# LNetPanel.net
KiCad netlist of a schematic drawn in EAGLE
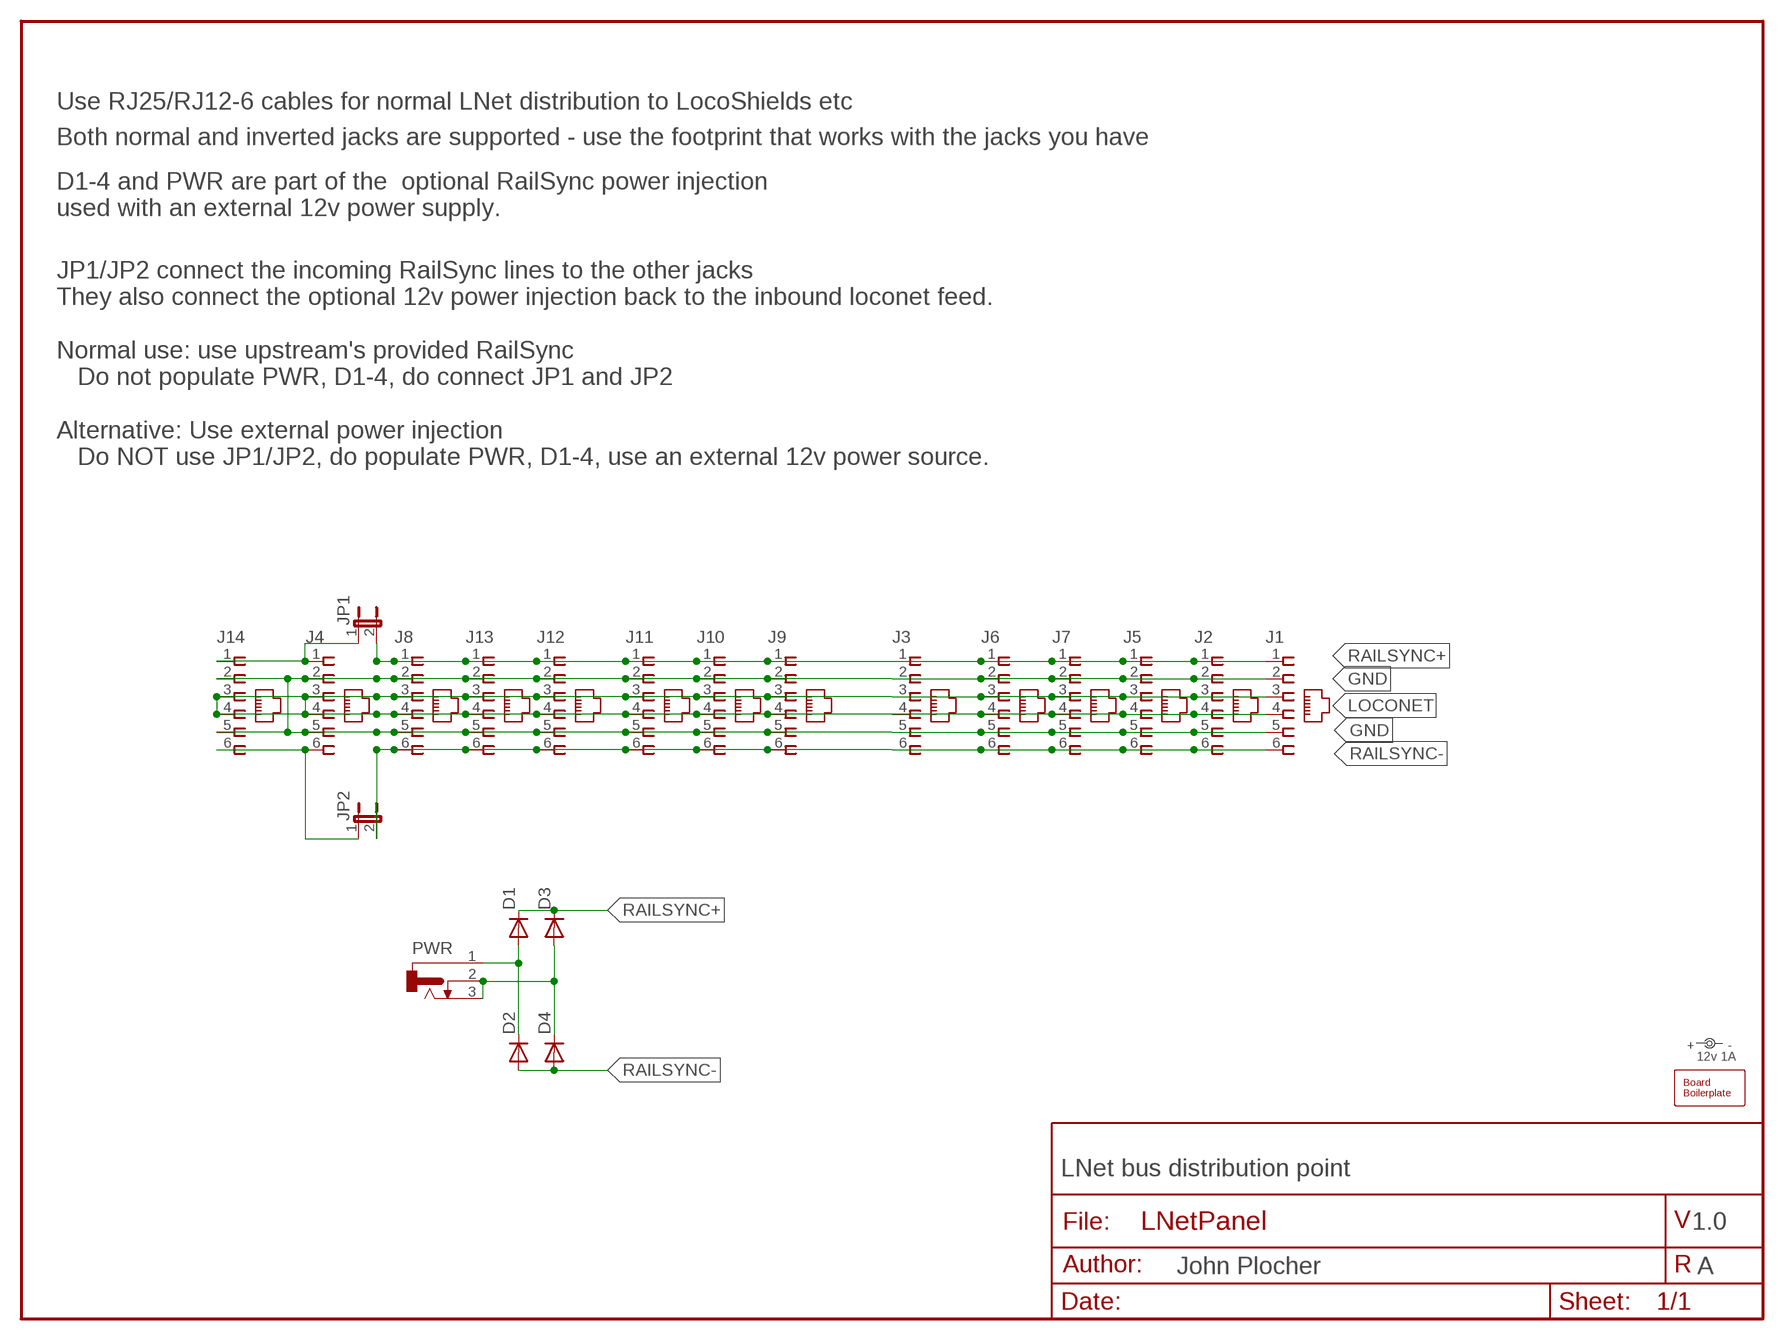
[diagram p0: schematic, sheet 1]

(export (version "E")
  (design (tool "Eeschema 10.0.6"))
  (components
    (comp (ref "D1")
      (value "DIODEPTH")
      (footprint "eagle-import:DIODE-1N4001")
      (libsource (lib "eagle-import") (part "DIODEPTH"))
    )
    (comp (ref "D2")
      (value "DIODEPTH")
      (footprint "eagle-import:DIODE-1N4001")
      (libsource (lib "eagle-import") (part "DIODEPTH"))
    )
    (comp (ref "D3")
      (value "DIODEPTH")
      (footprint "eagle-import:DIODE-1N4001")
      (libsource (lib "eagle-import") (part "DIODEPTH"))
    )
    (comp (ref "D4")
      (value "DIODEPTH")
      (footprint "eagle-import:DIODE-1N4001")
      (libsource (lib "eagle-import") (part "DIODEPTH"))
    )
    (comp (ref "J1")
      (value "CONNECTOR-RJ25-43860-2-MOLEX")
      (footprint "eagle-import:RJ25-INVERTED")
      (libsource (lib "eagle-import") (part "CONNECTOR-RJ25-43860-2-MOLEX"))
    )
    (comp (ref "J2")
      (value "CONNECTOR-RJ25-43860-2-MOLEX")
      (footprint "eagle-import:RJ25-INVERTED")
      (libsource (lib "eagle-import") (part "CONNECTOR-RJ25-43860-2-MOLEX"))
    )
    (comp (ref "J3")
      (value "CONNECTOR-RJ25-43860-2-MOLEX")
      (footprint "eagle-import:RJ25-INVERTED")
      (libsource (lib "eagle-import") (part "CONNECTOR-RJ25-43860-2-MOLEX"))
    )
    (comp (ref "J4")
      (value "CONNECTOR-RJ25-43860-2-MOLEX")
      (footprint "eagle-import:RJ25-INVERTED")
      (libsource (lib "eagle-import") (part "CONNECTOR-RJ25-43860-2-MOLEX"))
    )
    (comp (ref "J5")
      (value "CONNECTOR-RJ25-43860-2-MOLEX")
      (footprint "eagle-import:RJ25-INVERTED")
      (libsource (lib "eagle-import") (part "CONNECTOR-RJ25-43860-2-MOLEX"))
    )
    (comp (ref "J6")
      (value "CONNECTOR-RJ25-43860-2-MOLEX")
      (footprint "eagle-import:RJ25-INVERTED")
      (libsource (lib "eagle-import") (part "CONNECTOR-RJ25-43860-2-MOLEX"))
    )
    (comp (ref "J7")
      (value "CONNECTOR-RJ25-43860-2-MOLEX")
      (footprint "eagle-import:RJ25-INVERTED")
      (libsource (lib "eagle-import") (part "CONNECTOR-RJ25-43860-2-MOLEX"))
    )
    (comp (ref "J8")
      (value "CONNECTOR-RJ25AMP")
      (footprint "eagle-import:RJ25-PANEL")
      (libsource (lib "eagle-import") (part "CONNECTOR-RJ25AMP"))
    )
    (comp (ref "J9")
      (value "CONNECTOR-RJ25AMP")
      (footprint "eagle-import:RJ25-PANEL")
      (libsource (lib "eagle-import") (part "CONNECTOR-RJ25AMP"))
    )
    (comp (ref "J10")
      (value "CONNECTOR-RJ25AMP")
      (footprint "eagle-import:RJ25-PANEL")
      (libsource (lib "eagle-import") (part "CONNECTOR-RJ25AMP"))
    )
    (comp (ref "J11")
      (value "CONNECTOR-RJ25AMP")
      (footprint "eagle-import:RJ25-PANEL")
      (libsource (lib "eagle-import") (part "CONNECTOR-RJ25AMP"))
    )
    (comp (ref "J12")
      (value "CONNECTOR-RJ25AMP")
      (footprint "eagle-import:RJ25-PANEL")
      (libsource (lib "eagle-import") (part "CONNECTOR-RJ25AMP"))
    )
    (comp (ref "J13")
      (value "CONNECTOR-RJ25AMP")
      (footprint "eagle-import:RJ25-PANEL")
      (libsource (lib "eagle-import") (part "CONNECTOR-RJ25AMP"))
    )
    (comp (ref "J14")
      (value "CONNECTOR-RJ25AMP")
      (footprint "eagle-import:RJ25-PANEL")
      (libsource (lib "eagle-import") (part "CONNECTOR-RJ25AMP"))
    )
    (comp (ref "JP1")
      (value "JUMPER-2PTH_LOCK")
      (footprint "eagle-import:1X02_LOCK")
      (libsource (lib "eagle-import") (part "JUMPER-2PTH_LOCK"))
    )
    (comp (ref "JP2")
      (value "JUMPER-2PTH_LOCK")
      (footprint "eagle-import:1X02_LOCK")
      (libsource (lib "eagle-import") (part "JUMPER-2PTH_LOCK"))
    )
    (comp (ref "PWR")
      (value "CONNECTOR-DC-POWER-RA")
      (footprint "eagle-import:DCJ0202")
      (libsource (lib "eagle-import") (part "CONNECTOR-DC-POWER-RA"))
    )
    (comp (ref "U$1")
      (value "BOARD50X50-HOHOLES")
      (footprint "eagle-import:BOARD-SEEED7X7")
      (libsource (lib "eagle-import") (part "BOARD70X70"))
    )
    (comp (ref "U$2")
      (value "12v 1A")
      (footprint "eagle-import:POWER_USAGE")
      (libsource (lib "eagle-import") (part "DOC-POWER_LABEL"))
    )
  )
  (nets
    (net (code "1") (name "GND") (class "Default")
      (node (ref "J1") (pin "2") (pinfunction "2_2") (pintype "passive"))
      (node (ref "J1") (pin "5") (pinfunction "5_5") (pintype "passive"))
      (node (ref "J10") (pin "2") (pinfunction "2_2") (pintype "passive"))
      (node (ref "J10") (pin "5") (pinfunction "5_5") (pintype "passive"))
      (node (ref "J11") (pin "2") (pinfunction "2_2") (pintype "passive"))
      (node (ref "J11") (pin "5") (pinfunction "5_5") (pintype "passive"))
      (node (ref "J12") (pin "2") (pinfunction "2_2") (pintype "passive"))
      (node (ref "J12") (pin "5") (pinfunction "5_5") (pintype "passive"))
      (node (ref "J13") (pin "2") (pinfunction "2_2") (pintype "passive"))
      (node (ref "J13") (pin "5") (pinfunction "5_5") (pintype "passive"))
      (node (ref "J14") (pin "2") (pinfunction "2_2") (pintype "passive"))
      (node (ref "J14") (pin "5") (pinfunction "5_5") (pintype "passive"))
      (node (ref "J2") (pin "2") (pinfunction "2_2") (pintype "passive"))
      (node (ref "J2") (pin "5") (pinfunction "5_5") (pintype "passive"))
      (node (ref "J3") (pin "2") (pinfunction "2_2") (pintype "passive"))
      (node (ref "J3") (pin "5") (pinfunction "5_5") (pintype "passive"))
      (node (ref "J4") (pin "2") (pinfunction "2_2") (pintype "passive"))
      (node (ref "J4") (pin "5") (pinfunction "5_5") (pintype "passive"))
      (node (ref "J5") (pin "2") (pinfunction "2_2") (pintype "passive"))
      (node (ref "J5") (pin "5") (pinfunction "5_5") (pintype "passive"))
      (node (ref "J6") (pin "2") (pinfunction "2_2") (pintype "passive"))
      (node (ref "J6") (pin "5") (pinfunction "5_5") (pintype "passive"))
      (node (ref "J7") (pin "2") (pinfunction "2_2") (pintype "passive"))
      (node (ref "J7") (pin "5") (pinfunction "5_5") (pintype "passive"))
      (node (ref "J8") (pin "2") (pinfunction "2_2") (pintype "passive"))
      (node (ref "J8") (pin "5") (pinfunction "5_5") (pintype "passive"))
      (node (ref "J9") (pin "2") (pinfunction "2_2") (pintype "passive"))
      (node (ref "J9") (pin "5") (pinfunction "5_5") (pintype "passive"))
    )
    (net (code "2") (name "LOCONET") (class "Default")
      (node (ref "J1") (pin "3") (pinfunction "3_3") (pintype "passive"))
      (node (ref "J1") (pin "4") (pinfunction "4_4") (pintype "passive"))
      (node (ref "J10") (pin "3") (pinfunction "3_3") (pintype "passive"))
      (node (ref "J10") (pin "4") (pinfunction "4_4") (pintype "passive"))
      (node (ref "J11") (pin "3") (pinfunction "3_3") (pintype "passive"))
      (node (ref "J11") (pin "4") (pinfunction "4_4") (pintype "passive"))
      (node (ref "J12") (pin "3") (pinfunction "3_3") (pintype "passive"))
      (node (ref "J12") (pin "4") (pinfunction "4_4") (pintype "passive"))
      (node (ref "J13") (pin "3") (pinfunction "3_3") (pintype "passive"))
      (node (ref "J13") (pin "4") (pinfunction "4_4") (pintype "passive"))
      (node (ref "J14") (pin "3") (pinfunction "3_3") (pintype "passive"))
      (node (ref "J14") (pin "4") (pinfunction "4_4") (pintype "passive"))
      (node (ref "J2") (pin "3") (pinfunction "3_3") (pintype "passive"))
      (node (ref "J2") (pin "4") (pinfunction "4_4") (pintype "passive"))
      (node (ref "J3") (pin "3") (pinfunction "3_3") (pintype "passive"))
      (node (ref "J3") (pin "4") (pinfunction "4_4") (pintype "passive"))
      (node (ref "J4") (pin "3") (pinfunction "3_3") (pintype "passive"))
      (node (ref "J4") (pin "4") (pinfunction "4_4") (pintype "passive"))
      (node (ref "J5") (pin "3") (pinfunction "3_3") (pintype "passive"))
      (node (ref "J5") (pin "4") (pinfunction "4_4") (pintype "passive"))
      (node (ref "J6") (pin "3") (pinfunction "3_3") (pintype "passive"))
      (node (ref "J6") (pin "4") (pinfunction "4_4") (pintype "passive"))
      (node (ref "J7") (pin "3") (pinfunction "3_3") (pintype "passive"))
      (node (ref "J7") (pin "4") (pinfunction "4_4") (pintype "passive"))
      (node (ref "J8") (pin "3") (pinfunction "3_3") (pintype "passive"))
      (node (ref "J8") (pin "4") (pinfunction "4_4") (pintype "passive"))
      (node (ref "J9") (pin "3") (pinfunction "3_3") (pintype "passive"))
      (node (ref "J9") (pin "4") (pinfunction "4_4") (pintype "passive"))
    )
    (net (code "3") (name "Net-(D1-PadA)") (class "Default")
      (node (ref "D1") (pin "A") (pinfunction "A_A") (pintype "passive"))
      (node (ref "D2") (pin "C") (pinfunction "C_C") (pintype "passive"))
      (node (ref "PWR") (pin "1") (pinfunction "1_1") (pintype "passive"))
    )
    (net (code "4") (name "Net-(D3-PadA)") (class "Default")
      (node (ref "D3") (pin "A") (pinfunction "A_A") (pintype "passive"))
      (node (ref "D4") (pin "C") (pinfunction "C_C") (pintype "passive"))
      (node (ref "PWR") (pin "2") (pinfunction "2_2") (pintype "passive"))
      (node (ref "PWR") (pin "3") (pinfunction "3_3") (pintype "passive"))
    )
    (net (code "5") (name "Net-(J14-Pad1)") (class "Default")
      (node (ref "J14") (pin "1") (pinfunction "1_1") (pintype "passive"))
      (node (ref "J4") (pin "1") (pinfunction "1_1") (pintype "passive"))
      (node (ref "JP1") (pin "1") (pinfunction "1_1") (pintype "passive"))
    )
    (net (code "6") (name "Net-(J14-Pad6)") (class "Default")
      (node (ref "J14") (pin "6") (pinfunction "6_6") (pintype "passive"))
      (node (ref "J4") (pin "6") (pinfunction "6_6") (pintype "passive"))
      (node (ref "JP2") (pin "1") (pinfunction "1_1") (pintype "passive"))
    )
    (net (code "7") (name "RAILSYNC+") (class "Default")
      (node (ref "D1") (pin "C") (pinfunction "C_C") (pintype "passive"))
      (node (ref "D3") (pin "C") (pinfunction "C_C") (pintype "passive"))
      (node (ref "J1") (pin "1") (pinfunction "1_1") (pintype "passive"))
      (node (ref "J10") (pin "1") (pinfunction "1_1") (pintype "passive"))
      (node (ref "J11") (pin "1") (pinfunction "1_1") (pintype "passive"))
      (node (ref "J12") (pin "1") (pinfunction "1_1") (pintype "passive"))
      (node (ref "J13") (pin "1") (pinfunction "1_1") (pintype "passive"))
      (node (ref "J2") (pin "1") (pinfunction "1_1") (pintype "passive"))
      (node (ref "J3") (pin "1") (pinfunction "1_1") (pintype "passive"))
      (node (ref "J5") (pin "1") (pinfunction "1_1") (pintype "passive"))
      (node (ref "J6") (pin "1") (pinfunction "1_1") (pintype "passive"))
      (node (ref "J7") (pin "1") (pinfunction "1_1") (pintype "passive"))
      (node (ref "J8") (pin "1") (pinfunction "1_1") (pintype "passive"))
      (node (ref "J9") (pin "1") (pinfunction "1_1") (pintype "passive"))
      (node (ref "JP1") (pin "2") (pinfunction "2_2") (pintype "passive"))
    )
    (net (code "8") (name "RAILSYNC-") (class "Default")
      (node (ref "D2") (pin "A") (pinfunction "A_A") (pintype "passive"))
      (node (ref "D4") (pin "A") (pinfunction "A_A") (pintype "passive"))
      (node (ref "J1") (pin "6") (pinfunction "6_6") (pintype "passive"))
      (node (ref "J10") (pin "6") (pinfunction "6_6") (pintype "passive"))
      (node (ref "J11") (pin "6") (pinfunction "6_6") (pintype "passive"))
      (node (ref "J12") (pin "6") (pinfunction "6_6") (pintype "passive"))
      (node (ref "J13") (pin "6") (pinfunction "6_6") (pintype "passive"))
      (node (ref "J2") (pin "6") (pinfunction "6_6") (pintype "passive"))
      (node (ref "J3") (pin "6") (pinfunction "6_6") (pintype "passive"))
      (node (ref "J5") (pin "6") (pinfunction "6_6") (pintype "passive"))
      (node (ref "J6") (pin "6") (pinfunction "6_6") (pintype "passive"))
      (node (ref "J7") (pin "6") (pinfunction "6_6") (pintype "passive"))
      (node (ref "J8") (pin "6") (pinfunction "6_6") (pintype "passive"))
      (node (ref "J9") (pin "6") (pinfunction "6_6") (pintype "passive"))
      (node (ref "JP2") (pin "2") (pinfunction "2_2") (pintype "passive"))
    )
  )
)
